# power.net
KiCad netlist of a schematic drawn in Altium Designer
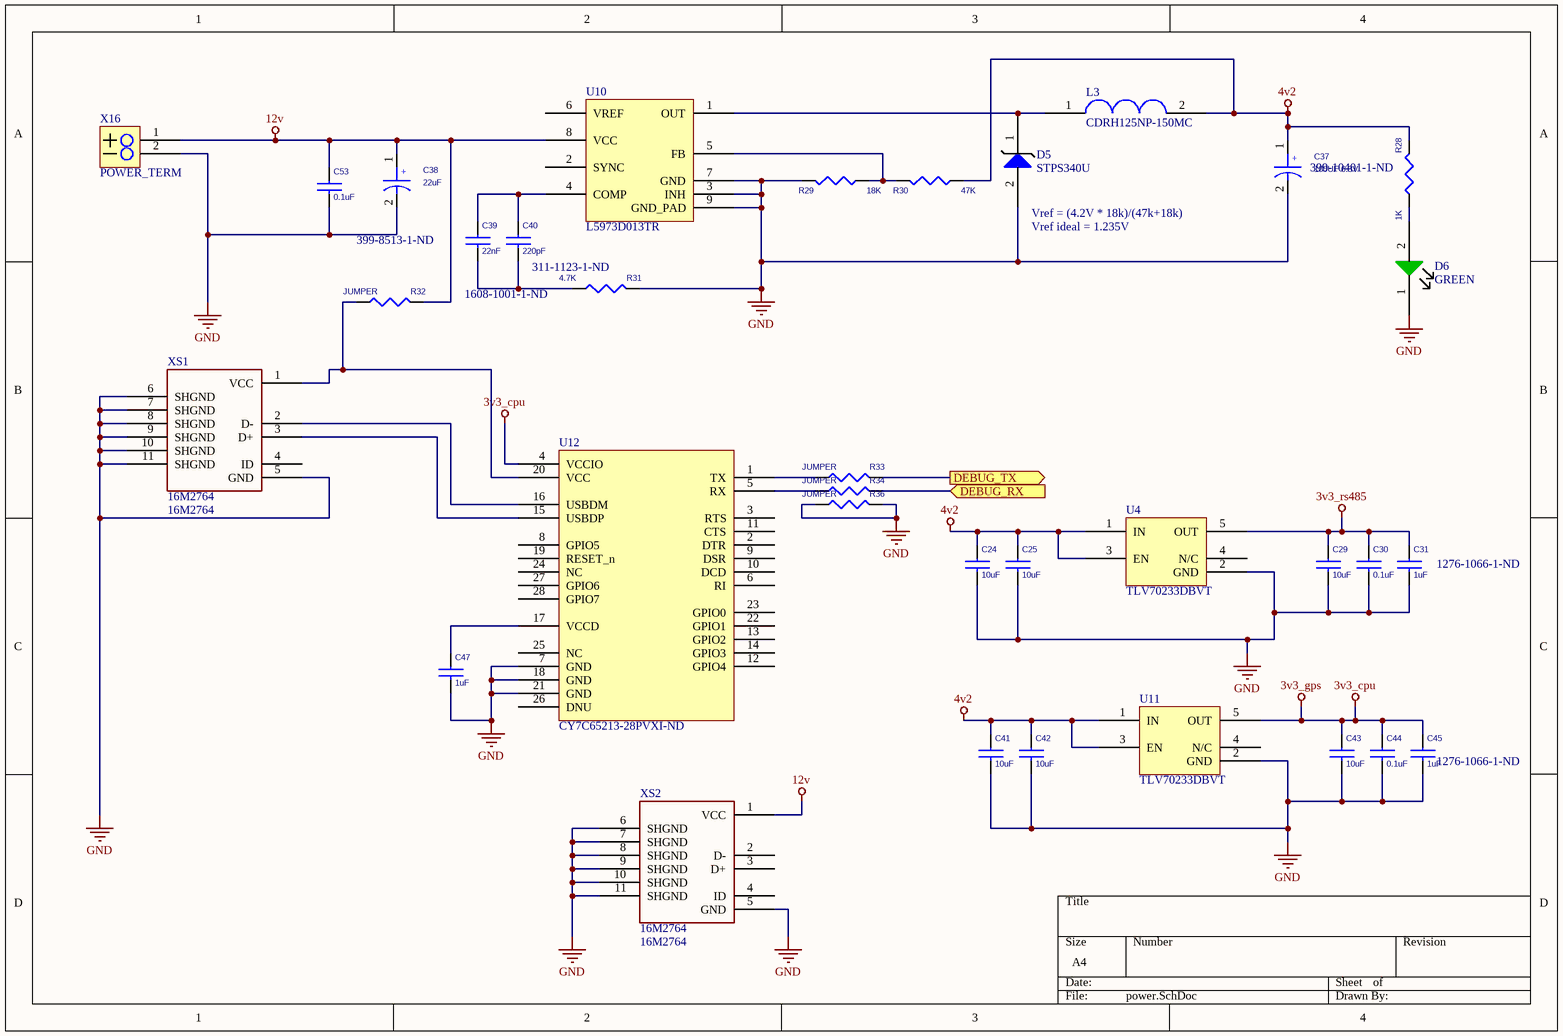
[diagram p0: power.SchDoc]

(export (version "E")
  (design (tool "Eeschema 10.0.6"))
  (components
    (comp (ref "C24")
      (value "10uF")
      (footprint "CAPC2012X09M")
      (description "CAP CER 10UF 16V 20% X5R 0805")
      (libsource (lib "Capacitors") (part "CAP_SMD_10UF_20%"))
    )
    (comp (ref "C25")
      (value "10uF")
      (footprint "CAPC2012X09M")
      (description "CAP CER 10UF 16V 20% X5R 0805")
      (libsource (lib "Capacitors") (part "CAP_SMD_10UF_20%"))
    )
    (comp (ref "C29")
      (value "10uF")
      (footprint "CAPC2012X09M")
      (description "CAP CER 10UF 16V 20% X5R 0805")
      (libsource (lib "Capacitors") (part "CAP_SMD_10UF_20%"))
    )
    (comp (ref "C30")
      (value "0.1uF")
      (footprint "CAPC2012X09M")
      (description "CAP CER 0.1UF 25V 10% X7R 0805")
      (libsource (lib "Capacitors") (part "CAP_SMD_0.1UF_10%"))
    )
    (comp (ref "C31")
      (value "1uF")
      (footprint "CAPC2012X09M")
      (description "MLCC; 1uF; 25V; X7R; ±10%; SMD; 0805;")
      (fields (field (name "SUPPLIER PART NUMBER 1") "1276-1066-1-ND"))
      (libsource (lib "Capacitors") (part "CAP_SMD_1uF_10%"))
    )
    (comp (ref "C37")
      (value "100UF 6.3V")
      (footprint "CAPMP6133X31N")
      (description "CAP 100uF; 6.3V; Case: C; ESR:150mOhm")
      (fields (field (name "SUPPLIER PART NUMBER 1") "399-10401-1-ND"))
      (libsource (lib "Capacitors") (part "CAP_SMD_100UF_10%"))
    )
    (comp (ref "C38")
      (value "22uF")
      (footprint "CAPMP7143X31N")
      (description "CAP SMD 35volts 22uF 10% ESR=300mOhms")
      (fields (field (name "SUPPLIER PART NUMBER 1") "399-8513-1-ND"))
      (libsource (lib "Capacitors") (part "CAP_SMD_22UF_10%"))
    )
    (comp (ref "C39")
      (value "22nF")
      (footprint "CAPC2012X09M")
      (description "CAP 22NF 50V 10% X7R 0805")
      (fields (field (name "SUPPLIER PART NUMBER 1") "1608-1001-1-ND"))
      (libsource (lib "Capacitors") (part "CAP_SMD_22nF_10%"))
    )
    (comp (ref "C40")
      (value "220pF")
      (footprint "CAPC2012X09M")
      (description "CAP 220PF 50V 10%  0805")
      (fields (field (name "SUPPLIER PART NUMBER 1") "311-1123-1-ND"))
      (libsource (lib "Capacitors") (part "CAP_SMD_220pF_10%"))
    )
    (comp (ref "C41")
      (value "10uF")
      (footprint "CAPC2012X09M")
      (description "CAP CER 10UF 16V 20% X5R 0805")
      (libsource (lib "Capacitors") (part "CAP_SMD_10UF_20%"))
    )
    (comp (ref "C42")
      (value "10uF")
      (footprint "CAPC2012X09M")
      (description "CAP CER 10UF 16V 20% X5R 0805")
      (libsource (lib "Capacitors") (part "CAP_SMD_10UF_20%"))
    )
    (comp (ref "C43")
      (value "10uF")
      (footprint "CAPC2012X09M")
      (description "CAP CER 10UF 16V 20% X5R 0805")
      (libsource (lib "Capacitors") (part "CAP_SMD_10UF_20%"))
    )
    (comp (ref "C44")
      (value "0.1uF")
      (footprint "CAPC2012X09M")
      (description "CAP CER 0.1UF 25V 10% X7R 0805")
      (libsource (lib "Capacitors") (part "CAP_SMD_0.1UF_10%"))
    )
    (comp (ref "C45")
      (value "1uF")
      (footprint "CAPC2012X09M")
      (description "MLCC; 1uF; 25V; X7R; ±10%; SMD; 0805;")
      (fields (field (name "SUPPLIER PART NUMBER 1") "1276-1066-1-ND"))
      (libsource (lib "Capacitors") (part "CAP_SMD_1uF_10%"))
    )
    (comp (ref "C47")
      (value "1uF")
      (footprint "CAPC2012X09M")
      (description "MLCC; 1uF; 25V; X7R; ±10%; SMD; 0805;")
      (libsource (lib "Capacitors") (part "CAP_SMD_1uF_10%"))
    )
    (comp (ref "C53")
      (value "0.1uF")
      (footprint "CAPC2012X09M")
      (description "CAP CER 0.1UF 25V 10% X7R 0805")
      (libsource (lib "Capacitors") (part "CAP_SMD_0.1UF_10%"))
    )
    (comp (ref "D5")
      (value "STPS340U")
      (footprint "SODFL535X265-2N")
      (description "DIODE, ZENER, 20V, 3W")
      (libsource (lib "Passive") (part "STPS340U"))
    )
    (comp (ref "D6")
      (value "GREEN")
      (footprint "DIOC2012X11N")
      (libsource (lib "Passive") (part "LED_GREEN"))
    )
    (comp (ref "L3")
      (value "CDRH125NP-150MC")
      (footprint "INDP123123X40N_SUMIDA")
      (libsource (lib "Passive") (part "IND_15uH_3.3A"))
    )
    (comp (ref "R28")
      (value "1K")
      (footprint "RESC2013X06M")
      (description "RES - 1K OHM, 5%, 1/8W, 0805 SMD")
      (libsource (lib "Resistors") (part "RES_SMD_1K_5%"))
    )
    (comp (ref "R29")
      (value "18K")
      (footprint "RESC2013X06M")
      (description "RES 18K OHM 1/8W 1% 0805 SMD")
      (libsource (lib "Resistors") (part "RES_SMD_18K_1%"))
    )
    (comp (ref "R30")
      (value "47K")
      (footprint "RESC2013X06M")
      (description "RES 47K OHM 1/8W 1% 0805")
      (libsource (lib "Resistors") (part "RES_SMD_47K_1%"))
    )
    (comp (ref "R31")
      (value "4.7K")
      (footprint "RESC2013X06M")
      (description "RES 4.7K OHM 1/8W 1% 0805 SMD")
      (libsource (lib "Resistors") (part "RES_SMD_4.7K_1%"))
    )
    (comp (ref "R32")
      (value "JUMPER")
      (footprint "RESC2013X06M_CMEASURE")
      (description "RES 0.0 OHM 1/8W JUMP 0805 SMD")
      (libsource (lib "Resistors") (part "RES_SMD_0_CURRENT"))
    )
    (comp (ref "R33")
      (value "JUMPER")
      (footprint "RESC2013X06M_CMEASURE")
      (description "RES 0.0 OHM 1/8W JUMP 0805 SMD")
      (libsource (lib "Resistors") (part "RES_SMD_0_CURRENT"))
    )
    (comp (ref "R34")
      (value "JUMPER")
      (footprint "RESC2013X06M_CMEASURE")
      (description "RES 0.0 OHM 1/8W JUMP 0805 SMD")
      (libsource (lib "Resistors") (part "RES_SMD_0_CURRENT"))
    )
    (comp (ref "R36")
      (value "JUMPER")
      (footprint "RESC2013X06M_CMEASURE")
      (description "RES 0.0 OHM 1/8W JUMP 0805 SMD")
      (libsource (lib "Resistors") (part "RES_SMD_0_CURRENT"))
    )
    (comp (ref "U4")
      (value "TLV70233DBVT")
      (footprint "SOT95P280X145-5M")
      (libsource (lib "TruthEar") (part "TLV70233DBVT"))
    )
    (comp (ref "U10")
      (value "L5973D013TR")
      (footprint "SOIC127P600X175_HS-9N")
      (description "IC REG BUCK ADJ 2.5A SOIC8")
      (libsource (lib "TruthEar") (part "L5973D013TR"))
    )
    (comp (ref "U11")
      (value "TLV70233DBVT")
      (footprint "SOT95P280X145-5M")
      (libsource (lib "TruthEar") (part "TLV70233DBVT"))
    )
    (comp (ref "U12")
      (value "CY7C65213")
      (footprint "SOP65P780X200-28M")
      (fields (field (name "SUPPLIER PART NUMBER 1") "CY7C65213-28PVXI-ND"))
      (libsource (lib "TruthEar") (part "CY7C65213"))
    )
    (comp (ref "X16")
      (value "POWER_TERM")
      (footprint "PH5")
      (libsource (lib "Connectors") (part "POWER_TERM"))
    )
    (comp (ref "XS1")
      (value "16M2764")
      (footprint "USB_MINI_16M2764")
      (fields (field (name "SUPPLIER PART NUMBER 1") "16M2764"))
      (libsource (lib "Connectors") (part "USB_MINI_16M2764"))
    )
    (comp (ref "XS2")
      (value "16M2764")
      (footprint "USB_MINI_16M2764")
      (fields (field (name "SUPPLIER PART NUMBER 1") "16M2764"))
      (libsource (lib "Connectors") (part "USB_MINI_16M2764"))
    )
  )
  (nets
    (net (code "1") (name "/DEBUG_RX") (class "Default")
      (node (ref "R34") (pin "2") (pinfunction "2_2") (pintype "passive"))
    )
    (net (code "2") (name "/DEBUG_TX") (class "Default")
      (node (ref "R33") (pin "2") (pinfunction "2_2") (pintype "passive"))
    )
    (net (code "3") (name "3v3_cpu") (class "Default")
      (node (ref "C43") (pin "1") (pinfunction "1_1") (pintype "passive"))
      (node (ref "C44") (pin "1") (pinfunction "1_1") (pintype "passive"))
      (node (ref "C45") (pin "1") (pinfunction "1_1") (pintype "passive"))
      (node (ref "U11") (pin "5") (pinfunction "OUT_5") (pintype "passive"))
      (node (ref "U12") (pin "4") (pinfunction "VCCIO_4") (pintype "power_in"))
    )
    (net (code "4") (name "3v3_rs485") (class "Default")
      (node (ref "C29") (pin "1") (pinfunction "1_1") (pintype "passive"))
      (node (ref "C30") (pin "1") (pinfunction "1_1") (pintype "passive"))
      (node (ref "C31") (pin "1") (pinfunction "1_1") (pintype "passive"))
      (node (ref "U4") (pin "5") (pinfunction "OUT_5") (pintype "passive"))
    )
    (net (code "5") (name "4v2") (class "Default")
      (node (ref "C24") (pin "1") (pinfunction "1_1") (pintype "passive"))
      (node (ref "C25") (pin "1") (pinfunction "1_1") (pintype "passive"))
      (node (ref "C37") (pin "1") (pinfunction "1_1") (pintype "passive"))
      (node (ref "C41") (pin "1") (pinfunction "1_1") (pintype "passive"))
      (node (ref "C42") (pin "1") (pinfunction "1_1") (pintype "passive"))
      (node (ref "L3") (pin "2") (pinfunction "2_2") (pintype "passive"))
      (node (ref "R28") (pin "2") (pinfunction "2_2") (pintype "passive"))
      (node (ref "R30") (pin "1") (pinfunction "1_1") (pintype "passive"))
      (node (ref "U11") (pin "1") (pinfunction "IN_1") (pintype "passive"))
      (node (ref "U11") (pin "3") (pinfunction "EN_3") (pintype "passive"))
      (node (ref "U4") (pin "1") (pinfunction "IN_1") (pintype "passive"))
      (node (ref "U4") (pin "3") (pinfunction "EN_3") (pintype "passive"))
    )
    (net (code "6") (name "12v") (class "Default")
      (node (ref "C38") (pin "1") (pinfunction "1_1") (pintype "passive"))
      (node (ref "C53") (pin "1") (pinfunction "1_1") (pintype "passive"))
      (node (ref "R32") (pin "2") (pinfunction "2_2") (pintype "passive"))
      (node (ref "U10") (pin "8") (pinfunction "VCC_8") (pintype "passive"))
      (node (ref "X16") (pin "1") (pinfunction "1_1") (pintype "passive"))
      (node (ref "XS2") (pin "1") (pinfunction "VCC_1") (pintype "passive"))
    )
    (net (code "7") (name "GND") (class "Default")
      (node (ref "C24") (pin "2") (pinfunction "2_2") (pintype "passive"))
      (node (ref "C25") (pin "2") (pinfunction "2_2") (pintype "passive"))
      (node (ref "C29") (pin "2") (pinfunction "2_2") (pintype "passive"))
      (node (ref "C30") (pin "2") (pinfunction "2_2") (pintype "passive"))
      (node (ref "C31") (pin "2") (pinfunction "2_2") (pintype "passive"))
      (node (ref "C37") (pin "2") (pinfunction "2_2") (pintype "passive"))
      (node (ref "C38") (pin "2") (pinfunction "2_2") (pintype "passive"))
      (node (ref "C41") (pin "2") (pinfunction "2_2") (pintype "passive"))
      (node (ref "C42") (pin "2") (pinfunction "2_2") (pintype "passive"))
      (node (ref "C43") (pin "2") (pinfunction "2_2") (pintype "passive"))
      (node (ref "C44") (pin "2") (pinfunction "2_2") (pintype "passive"))
      (node (ref "C45") (pin "2") (pinfunction "2_2") (pintype "passive"))
      (node (ref "C47") (pin "2") (pinfunction "2_2") (pintype "passive"))
      (node (ref "C53") (pin "2") (pinfunction "2_2") (pintype "passive"))
      (node (ref "D5") (pin "2") (pinfunction "A_2") (pintype "passive"))
      (node (ref "D6") (pin "1") (pinfunction "C_1") (pintype "passive"))
      (node (ref "R29") (pin "2") (pinfunction "2_2") (pintype "passive"))
      (node (ref "R31") (pin "2") (pinfunction "2_2") (pintype "passive"))
      (node (ref "R36") (pin "1") (pinfunction "1_1") (pintype "passive"))
      (node (ref "R36") (pin "2") (pinfunction "2_2") (pintype "passive"))
      (node (ref "U10") (pin "3") (pinfunction "INH_3") (pintype "passive"))
      (node (ref "U10") (pin "7") (pinfunction "GND_7") (pintype "passive"))
      (node (ref "U10") (pin "9") (pinfunction "GND_PAD_9") (pintype "passive"))
      (node (ref "U11") (pin "2") (pinfunction "GND_2") (pintype "passive"))
      (node (ref "U12") (pin "18") (pinfunction "GND_18") (pintype "power_in"))
      (node (ref "U12") (pin "21") (pinfunction "GND_21") (pintype "power_in"))
      (node (ref "U12") (pin "7") (pinfunction "GND_7") (pintype "power_in"))
      (node (ref "U4") (pin "2") (pinfunction "GND_2") (pintype "passive"))
      (node (ref "X16") (pin "2") (pinfunction "2_2") (pintype "passive"))
      (node (ref "XS1") (pin "10") (pinfunction "SHGND_10") (pintype "passive"))
      (node (ref "XS1") (pin "11") (pinfunction "SHGND_11") (pintype "passive"))
      (node (ref "XS1") (pin "5") (pinfunction "GND_5") (pintype "passive"))
      (node (ref "XS1") (pin "6") (pinfunction "SHGND_6") (pintype "passive"))
      (node (ref "XS1") (pin "7") (pinfunction "SHGND_7") (pintype "passive"))
      (node (ref "XS1") (pin "8") (pinfunction "SHGND_8") (pintype "passive"))
      (node (ref "XS1") (pin "9") (pinfunction "SHGND_9") (pintype "passive"))
      (node (ref "XS2") (pin "10") (pinfunction "SHGND_10") (pintype "passive"))
      (node (ref "XS2") (pin "11") (pinfunction "SHGND_11") (pintype "passive"))
      (node (ref "XS2") (pin "5") (pinfunction "GND_5") (pintype "passive"))
      (node (ref "XS2") (pin "6") (pinfunction "SHGND_6") (pintype "passive"))
      (node (ref "XS2") (pin "7") (pinfunction "SHGND_7") (pintype "passive"))
      (node (ref "XS2") (pin "8") (pinfunction "SHGND_8") (pintype "passive"))
      (node (ref "XS2") (pin "9") (pinfunction "SHGND_9") (pintype "passive"))
    )
    (net (code "8") (name "Net-(C39-Pad2)") (class "Default")
      (node (ref "C39") (pin "2") (pinfunction "2_2") (pintype "passive"))
      (node (ref "C40") (pin "2") (pinfunction "2_2") (pintype "passive"))
      (node (ref "R31") (pin "1") (pinfunction "1_1") (pintype "passive"))
    )
    (net (code "9") (name "Net-(D5-C)") (class "Default")
      (node (ref "D5") (pin "1") (pinfunction "C_1") (pintype "passive"))
      (node (ref "L3") (pin "1") (pinfunction "1_1") (pintype "passive"))
      (node (ref "U10") (pin "1") (pinfunction "OUT_1") (pintype "passive"))
    )
    (net (code "10") (name "Net-(D6-A)") (class "Default")
      (node (ref "D6") (pin "2") (pinfunction "A_2") (pintype "passive"))
      (node (ref "R28") (pin "1") (pinfunction "1_1") (pintype "passive"))
    )
    (net (code "11") (name "Net-(U10-COMP)") (class "Default")
      (node (ref "C39") (pin "1") (pinfunction "1_1") (pintype "passive"))
      (node (ref "C40") (pin "1") (pinfunction "1_1") (pintype "passive"))
      (node (ref "U10") (pin "4") (pinfunction "COMP_4") (pintype "passive"))
    )
    (net (code "12") (name "Net-(U10-FB)") (class "Default")
      (node (ref "R29") (pin "1") (pinfunction "1_1") (pintype "passive"))
      (node (ref "R30") (pin "2") (pinfunction "2_2") (pintype "passive"))
      (node (ref "U10") (pin "5") (pinfunction "FB_5") (pintype "passive"))
    )
    (net (code "13") (name "Net-(U12-RX)") (class "Default")
      (node (ref "R34") (pin "1") (pinfunction "1_1") (pintype "passive"))
      (node (ref "U12") (pin "5") (pinfunction "RX_5") (pintype "power_in"))
    )
    (net (code "14") (name "Net-(U12-TX)") (class "Default")
      (node (ref "R33") (pin "1") (pinfunction "1_1") (pintype "passive"))
      (node (ref "U12") (pin "1") (pinfunction "TX_1") (pintype "power_in"))
    )
    (net (code "15") (name "Net-(U12-USBDM)") (class "Default")
      (node (ref "U12") (pin "16") (pinfunction "USBDM_16") (pintype "power_in"))
      (node (ref "XS1") (pin "2") (pinfunction "D-_2") (pintype "passive"))
    )
    (net (code "16") (name "Net-(U12-USBDP)") (class "Default")
      (node (ref "U12") (pin "15") (pinfunction "USBDP_15") (pintype "power_in"))
      (node (ref "XS1") (pin "3") (pinfunction "D+_3") (pintype "passive"))
    )
    (net (code "17") (name "Net-(U12-VCC)") (class "Default")
      (node (ref "R32") (pin "1") (pinfunction "1_1") (pintype "passive"))
      (node (ref "U12") (pin "20") (pinfunction "VCC_20") (pintype "power_in"))
      (node (ref "XS1") (pin "1") (pinfunction "VCC_1") (pintype "passive"))
    )
    (net (code "18") (name "Net-(U12-VCCD)") (class "Default")
      (node (ref "C47") (pin "1") (pinfunction "1_1") (pintype "passive"))
      (node (ref "U12") (pin "17") (pinfunction "VCCD_17") (pintype "power_in"))
    )
    (net (code "19") (name "unconnected-(U4-N{slash}C-Pad4)") (class "Default")
      (node (ref "U4") (pin "4") (pinfunction "N/C_4") (pintype "passive"))
    )
    (net (code "20") (name "unconnected-(U10-SYNC-Pad2)") (class "Default")
      (node (ref "U10") (pin "2") (pinfunction "SYNC_2") (pintype "passive"))
    )
    (net (code "21") (name "unconnected-(U10-VREF-Pad6)") (class "Default")
      (node (ref "U10") (pin "6") (pinfunction "VREF_6") (pintype "passive"))
    )
    (net (code "22") (name "unconnected-(U11-N{slash}C-Pad4)") (class "Default")
      (node (ref "U11") (pin "4") (pinfunction "N/C_4") (pintype "passive"))
    )
    (net (code "23") (name "unconnected-(U12-CTS-Pad11)") (class "Default")
      (node (ref "U12") (pin "11") (pinfunction "CTS_11") (pintype "power_in"))
    )
    (net (code "24") (name "unconnected-(U12-DCD-Pad10)") (class "Default")
      (node (ref "U12") (pin "10") (pinfunction "DCD_10") (pintype "power_in"))
    )
    (net (code "25") (name "unconnected-(U12-DNU-Pad26)") (class "Default")
      (node (ref "U12") (pin "26") (pinfunction "DNU_26") (pintype "power_in"))
    )
    (net (code "26") (name "unconnected-(U12-DSR-Pad9)") (class "Default")
      (node (ref "U12") (pin "9") (pinfunction "DSR_9") (pintype "power_in"))
    )
    (net (code "27") (name "unconnected-(U12-DTR-Pad2)") (class "Default")
      (node (ref "U12") (pin "2") (pinfunction "DTR_2") (pintype "power_in"))
    )
    (net (code "28") (name "unconnected-(U12-GPIO0-Pad23)") (class "Default")
      (node (ref "U12") (pin "23") (pinfunction "GPIO0_23") (pintype "power_in"))
    )
    (net (code "29") (name "unconnected-(U12-GPIO1-Pad22)") (class "Default")
      (node (ref "U12") (pin "22") (pinfunction "GPIO1_22") (pintype "power_in"))
    )
    (net (code "30") (name "unconnected-(U12-GPIO2-Pad13)") (class "Default")
      (node (ref "U12") (pin "13") (pinfunction "GPIO2_13") (pintype "power_in"))
    )
    (net (code "31") (name "unconnected-(U12-GPIO3-Pad14)") (class "Default")
      (node (ref "U12") (pin "14") (pinfunction "GPIO3_14") (pintype "power_in"))
    )
    (net (code "32") (name "unconnected-(U12-GPIO4-Pad12)") (class "Default")
      (node (ref "U12") (pin "12") (pinfunction "GPIO4_12") (pintype "power_in"))
    )
    (net (code "33") (name "unconnected-(U12-GPIO5-Pad8)") (class "Default")
      (node (ref "U12") (pin "8") (pinfunction "GPIO5_8") (pintype "power_in"))
    )
    (net (code "34") (name "unconnected-(U12-GPIO6-Pad27)") (class "Default")
      (node (ref "U12") (pin "27") (pinfunction "GPIO6_27") (pintype "power_in"))
    )
    (net (code "35") (name "unconnected-(U12-GPIO7-Pad28)") (class "Default")
      (node (ref "U12") (pin "28") (pinfunction "GPIO7_28") (pintype "power_in"))
    )
    (net (code "36") (name "unconnected-(U12-NC-Pad24)") (class "Default")
      (node (ref "U12") (pin "24") (pinfunction "NC_24") (pintype "power_in"))
    )
    (net (code "37") (name "unconnected-(U12-NC-Pad25)") (class "Default")
      (node (ref "U12") (pin "25") (pinfunction "NC_25") (pintype "power_in"))
    )
    (net (code "38") (name "unconnected-(U12-RESET_n-Pad19)") (class "Default")
      (node (ref "U12") (pin "19") (pinfunction "RESET_n_19") (pintype "power_in"))
    )
    (net (code "39") (name "unconnected-(U12-RI-Pad6)") (class "Default")
      (node (ref "U12") (pin "6") (pinfunction "RI_6") (pintype "power_in"))
    )
    (net (code "40") (name "unconnected-(U12-RTS-Pad3)") (class "Default")
      (node (ref "U12") (pin "3") (pinfunction "RTS_3") (pintype "power_in"))
    )
    (net (code "41") (name "unconnected-(XS1-ID-Pad4)") (class "Default")
      (node (ref "XS1") (pin "4") (pinfunction "ID_4") (pintype "passive"))
    )
    (net (code "42") (name "unconnected-(XS2-D+-Pad3)") (class "Default")
      (node (ref "XS2") (pin "3") (pinfunction "D+_3") (pintype "passive"))
    )
    (net (code "43") (name "unconnected-(XS2-D--Pad2)") (class "Default")
      (node (ref "XS2") (pin "2") (pinfunction "D-_2") (pintype "passive"))
    )
    (net (code "44") (name "unconnected-(XS2-ID-Pad4)") (class "Default")
      (node (ref "XS2") (pin "4") (pinfunction "ID_4") (pintype "passive"))
    )
  )
)
